# MB_power_supply.net
KiCad netlist of a schematic drawn in Altium Designer
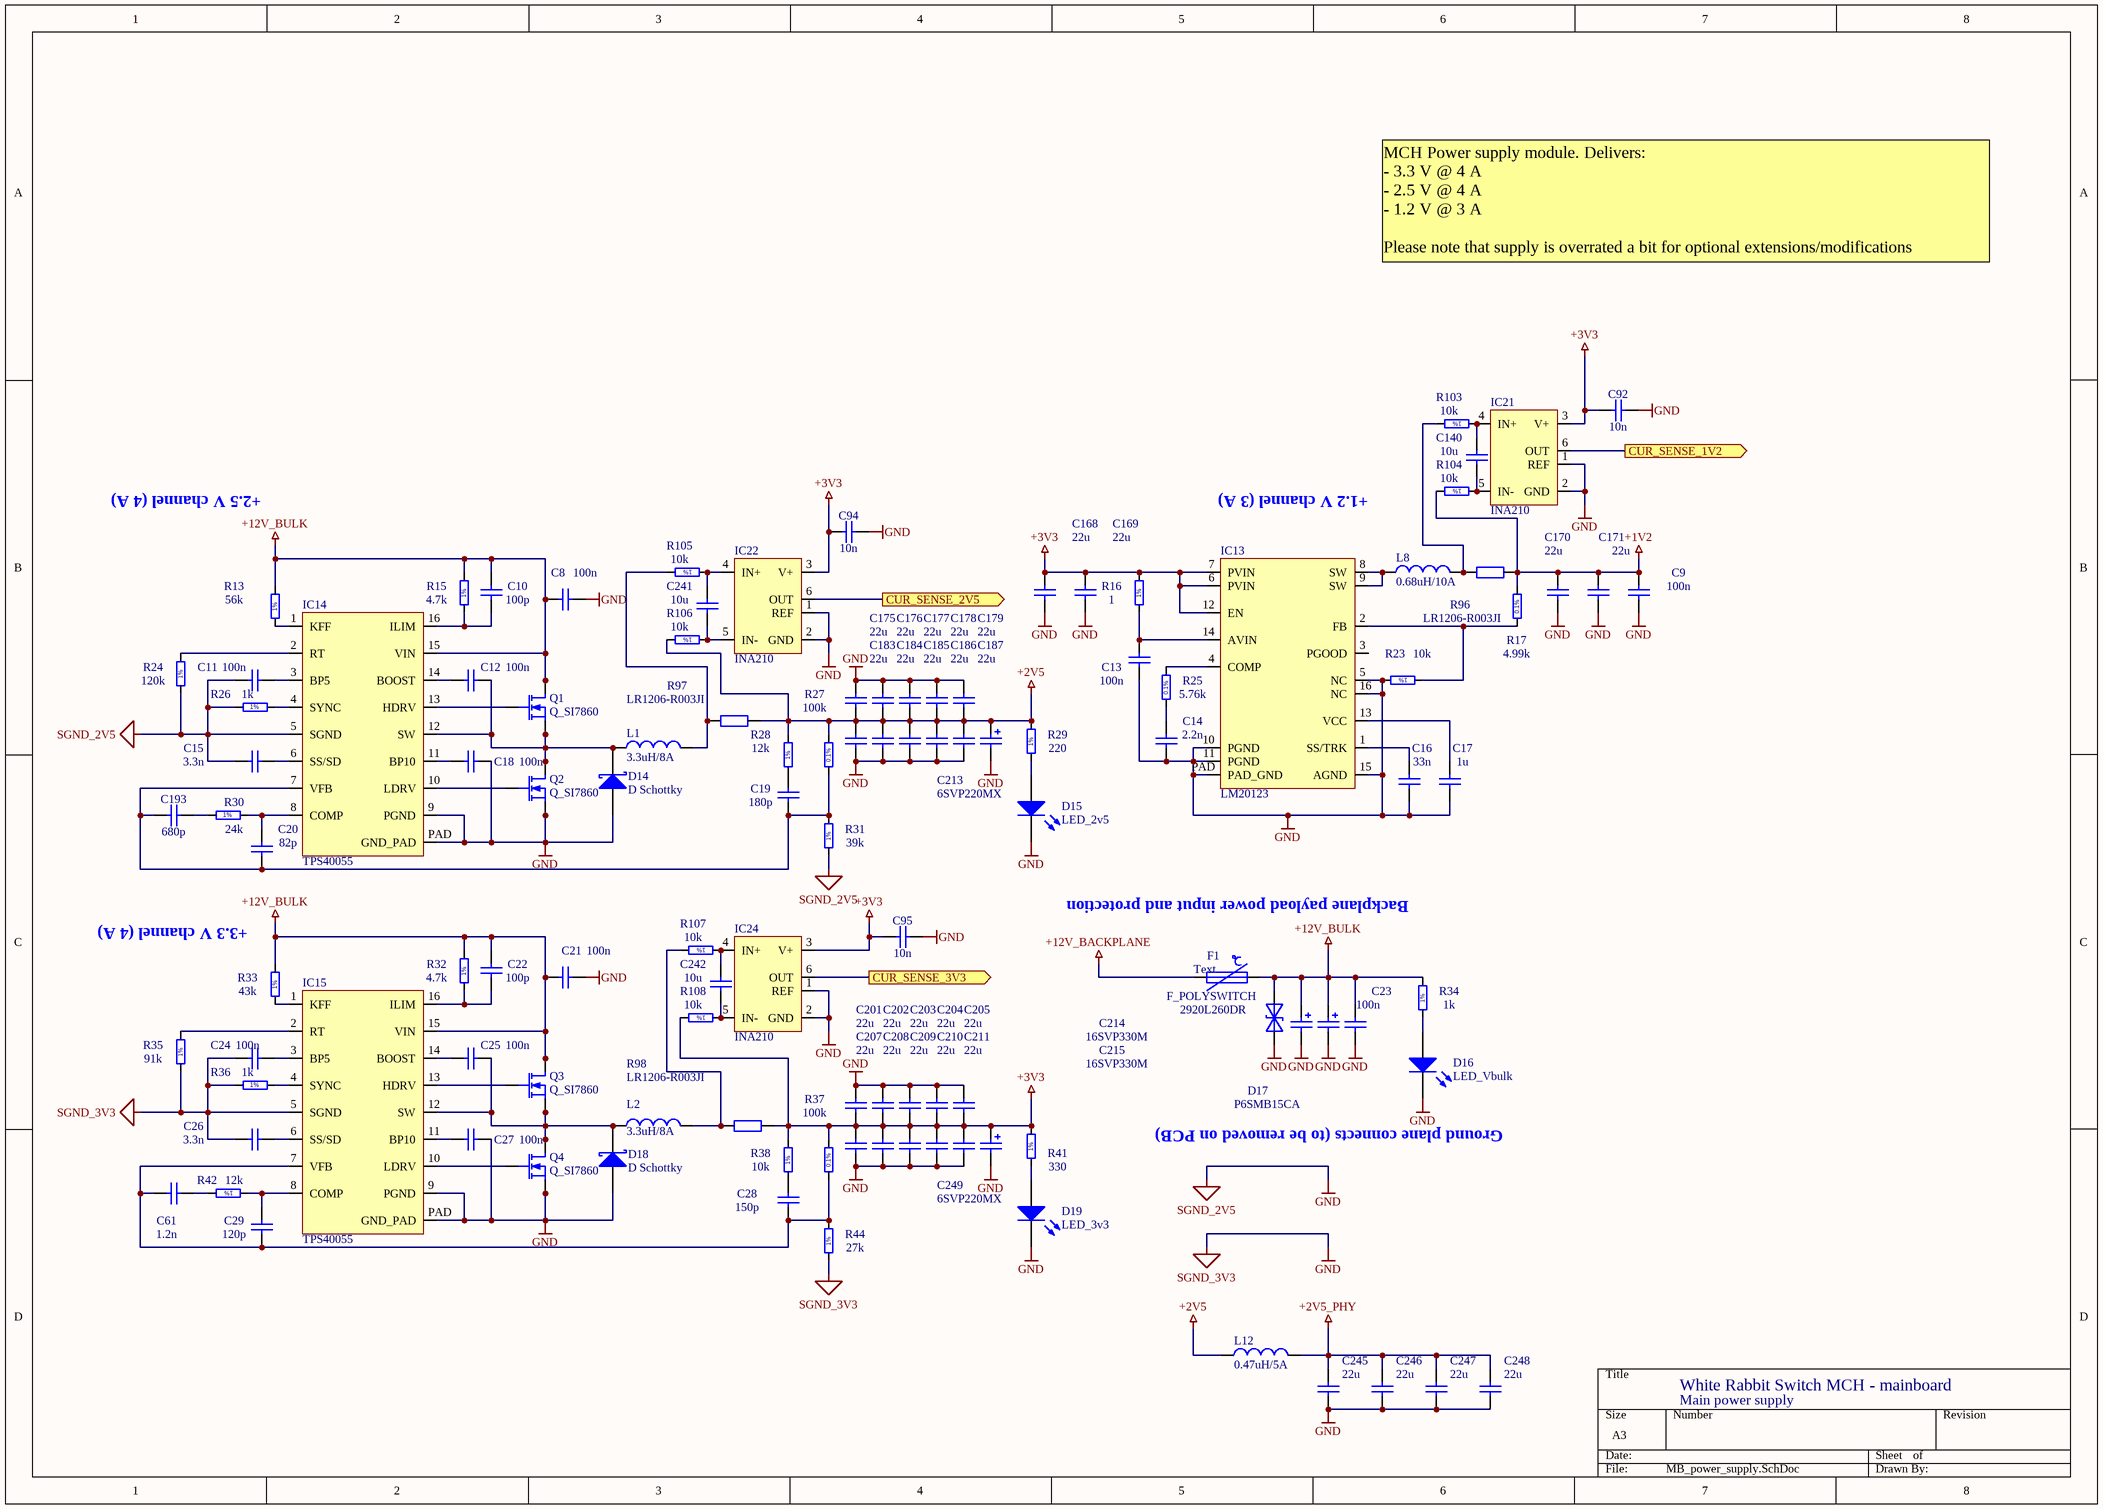
[diagram p0: MB_power_supply.SchDoc]

(export (version "E")
  (design (tool "Eeschema 10.0.6"))
  (components
    (comp (ref "C8")
      (value "100n")
      (footprint "CAPC1608X87N")
      (description "Non-polarised capacitor")
      (fields (field (name "PART NUMBER") "CC0603_100NF_50V_10%_X7R") (field (name "VOLTAGE") "50V"))
      (libsource (lib "Capacitors") (part "Capacitor - non polarized"))
    )
    (comp (ref "C9")
      (value "100n")
      (footprint "CAPC1608X87N")
      (description "Non-polarised capacitor")
      (fields (field (name "PART NUMBER") "CC0603_100NF_50V_10%_X7R") (field (name "VOLTAGE") "50V"))
      (libsource (lib "Capacitors") (part "Capacitor - non polarized"))
    )
    (comp (ref "C10")
      (value "100p")
      (footprint "CAPC1608X87N")
      (description "Non-polarised capacitor")
      (fields (field (name "PART NUMBER") "CC0603_100PF_50V_5%_NP0") (field (name "VOLTAGE") "50V"))
      (libsource (lib "Capacitors") (part "Capacitor - non polarized"))
    )
    (comp (ref "C11")
      (value "100n")
      (footprint "CAPC1608X87N")
      (description "Non-polarised capacitor")
      (fields (field (name "PART NUMBER") "CC0603_100NF_50V_10%_X7R") (field (name "VOLTAGE") "50V"))
      (libsource (lib "Capacitors") (part "Capacitor - non polarized"))
    )
    (comp (ref "C12")
      (value "100n")
      (footprint "CAPC1608X87N")
      (description "Non-polarised capacitor")
      (fields (field (name "PART NUMBER") "CC0603_100NF_50V_10%_X7R") (field (name "VOLTAGE") "50V"))
      (libsource (lib "Capacitors") (part "Capacitor - non polarized"))
    )
    (comp (ref "C13")
      (value "100n")
      (footprint "CAPC1608X87N")
      (description "Non-polarised capacitor")
      (fields (field (name "PART NUMBER") "CC0603_100NF_50V_10%_X7R") (field (name "VOLTAGE") "50V"))
      (libsource (lib "Capacitors") (part "Capacitor - non polarized"))
    )
    (comp (ref "C14")
      (value "2.2n")
      (footprint "CAPC1608X87N")
      (description "Non-polarised capacitor")
      (fields (field (name "PART NUMBER") "CC0603_2.2NF_50V_10%_X7R") (field (name "VOLTAGE") "50V"))
      (libsource (lib "Capacitors") (part "Capacitor - non polarized"))
    )
    (comp (ref "C15")
      (value "3.3n")
      (footprint "CAPC1608X87N")
      (description "Non-polarised capacitor")
      (fields (field (name "PART NUMBER") "CC0603_3.3NF_50V_10%_X7R") (field (name "VOLTAGE") "50V"))
      (libsource (lib "Capacitors") (part "Capacitor - non polarized"))
    )
    (comp (ref "C16")
      (value "33n")
      (footprint "CAPC1608X87N")
      (description "Non-polarised capacitor")
      (fields (field (name "PART NUMBER") "CC0603_33NF_25V_10%_X7R") (field (name "VOLTAGE") "25V"))
      (libsource (lib "Capacitors") (part "Capacitor - non polarized"))
    )
    (comp (ref "C17")
      (value "1u")
      (footprint "CAPC1608X87N")
      (description "Non-polarised capacitor")
      (fields (field (name "PART NUMBER") "CC0603_1.0uF_16V_10%_X7R") (field (name "VOLTAGE") "16V"))
      (libsource (lib "Capacitors") (part "Capacitor - non polarized"))
    )
    (comp (ref "C18")
      (value "100n")
      (footprint "CAPC1608X87N")
      (description "Non-polarised capacitor")
      (fields (field (name "PART NUMBER") "CC0603_100NF_50V_10%_X7R") (field (name "VOLTAGE") "50V"))
      (libsource (lib "Capacitors") (part "Capacitor - non polarized"))
    )
    (comp (ref "C19")
      (value "180p")
      (footprint "CAPC1608X87N")
      (description "Non-polarised capacitor")
      (fields (field (name "PART NUMBER") "CC0603_180PF_50V_5%_NP0") (field (name "VOLTAGE") "50V"))
      (libsource (lib "Capacitors") (part "Capacitor - non polarized"))
    )
    (comp (ref "C20")
      (value "82p")
      (footprint "CAPC1608X87N")
      (description "Non-polarised capacitor")
      (fields (field (name "PART NUMBER") "CC0603_82PF_50V_5%_NP0") (field (name "VOLTAGE") "50V"))
      (libsource (lib "Capacitors") (part "Capacitor - non polarized"))
    )
    (comp (ref "C21")
      (value "100n")
      (footprint "CAPC1608X87N")
      (description "Non-polarised capacitor")
      (fields (field (name "PART NUMBER") "CC0603_100NF_50V_10%_X7R") (field (name "VOLTAGE") "50V"))
      (libsource (lib "Capacitors") (part "Capacitor - non polarized"))
    )
    (comp (ref "C22")
      (value "100p")
      (footprint "CAPC1608X87N")
      (description "Non-polarised capacitor")
      (fields (field (name "PART NUMBER") "CC0603_100PF_50V_5%_NP0") (field (name "VOLTAGE") "50V"))
      (libsource (lib "Capacitors") (part "Capacitor - non polarized"))
    )
    (comp (ref "C23")
      (value "100n")
      (footprint "CAPC1608X87N")
      (description "Non-polarised capacitor")
      (fields (field (name "PART NUMBER") "CC0603_100NF_50V_10%_X7R") (field (name "VOLTAGE") "50V"))
      (libsource (lib "Capacitors") (part "Capacitor - non polarized"))
    )
    (comp (ref "C24")
      (value "100n")
      (footprint "CAPC1608X87N")
      (description "Non-polarised capacitor")
      (fields (field (name "PART NUMBER") "CC0603_100NF_50V_10%_X7R") (field (name "VOLTAGE") "50V"))
      (libsource (lib "Capacitors") (part "Capacitor - non polarized"))
    )
    (comp (ref "C25")
      (value "100n")
      (footprint "CAPC1608X87N")
      (description "Non-polarised capacitor")
      (fields (field (name "PART NUMBER") "CC0603_100NF_50V_10%_X7R") (field (name "VOLTAGE") "50V"))
      (libsource (lib "Capacitors") (part "Capacitor - non polarized"))
    )
    (comp (ref "C26")
      (value "3.3n")
      (footprint "CAPC1608X87N")
      (description "Non-polarised capacitor")
      (fields (field (name "PART NUMBER") "CC0603_3.3NF_50V_10%_X7R") (field (name "VOLTAGE") "50V"))
      (libsource (lib "Capacitors") (part "Capacitor - non polarized"))
    )
    (comp (ref "C27")
      (value "100n")
      (footprint "CAPC1608X87N")
      (description "Non-polarised capacitor")
      (fields (field (name "PART NUMBER") "CC0603_100NF_50V_10%_X7R") (field (name "VOLTAGE") "50V"))
      (libsource (lib "Capacitors") (part "Capacitor - non polarized"))
    )
    (comp (ref "C28")
      (value "150p")
      (footprint "CAPC1608X87N")
      (description "Non-polarised capacitor")
      (fields (field (name "PART NUMBER") "CC0603_150PF_50V_5%_NP0") (field (name "VOLTAGE") "50V"))
      (libsource (lib "Capacitors") (part "Capacitor - non polarized"))
    )
    (comp (ref "C29")
      (value "120p")
      (footprint "CAPC1608X87N")
      (description "Non-polarised capacitor")
      (fields (field (name "PART NUMBER") "CC0603_120PF_50V_5%_NP0") (field (name "VOLTAGE") "50V"))
      (libsource (lib "Capacitors") (part "Capacitor - non polarized"))
    )
    (comp (ref "C61")
      (value "1.2n")
      (footprint "CAPC1608X87N")
      (description "Non-polarised capacitor")
      (fields (field (name "PART NUMBER") "CC0603_1.2NF_50V_10%_X7R") (field (name "VOLTAGE") "50V"))
      (libsource (lib "Capacitors") (part "Capacitor - non polarized"))
    )
    (comp (ref "C92")
      (value "10n")
      (footprint "CAPC1608X87N")
      (description "Non-polarised capacitor")
      (fields (field (name "PART NUMBER") "CC0603_10NF_50V_10%_X7R") (field (name "VOLTAGE") "50V"))
      (libsource (lib "Capacitors") (part "Capacitor - non polarized"))
    )
    (comp (ref "C94")
      (value "10n")
      (footprint "CAPC1608X87N")
      (description "Non-polarised capacitor")
      (fields (field (name "PART NUMBER") "CC0603_10NF_50V_10%_X7R") (field (name "VOLTAGE") "50V"))
      (libsource (lib "Capacitors") (part "Capacitor - non polarized"))
    )
    (comp (ref "C95")
      (value "10n")
      (footprint "CAPC1608X87N")
      (description "Non-polarised capacitor")
      (fields (field (name "PART NUMBER") "CC0603_10NF_50V_10%_X7R") (field (name "VOLTAGE") "50V"))
      (libsource (lib "Capacitors") (part "Capacitor - non polarized"))
    )
    (comp (ref "C140")
      (value "10u")
      (footprint "CAPC1608X87N")
      (description "Non-polarised capacitor")
      (fields (field (name "PART NUMBER") "CC0603_10uF_6.3V_20%_X5R") (field (name "VOLTAGE") "6.3V"))
      (libsource (lib "Capacitors") (part "Capacitor - non polarized"))
    )
    (comp (ref "C168")
      (value "22u")
      (footprint "CC3216-1206")
      (description "Capacitor")
      (fields (field (name "Comment") "Cap"))
      (libsource (lib "wr_switch") (part "Cap"))
    )
    (comp (ref "C169")
      (value "22u")
      (footprint "CC3216-1206")
      (description "Capacitor")
      (fields (field (name "Comment") "Cap"))
      (libsource (lib "wr_switch") (part "Cap"))
    )
    (comp (ref "C170")
      (value "22u")
      (footprint "CC3216-1206")
      (description "Capacitor")
      (fields (field (name "Comment") "Cap"))
      (libsource (lib "wr_switch") (part "Cap"))
    )
    (comp (ref "C171")
      (value "22u")
      (footprint "CC3216-1206")
      (description "Capacitor")
      (fields (field (name "Comment") "Cap"))
      (libsource (lib "wr_switch") (part "Cap"))
    )
    (comp (ref "C175")
      (value "22u")
      (footprint "CC3216-1206")
      (description "Capacitor")
      (fields (field (name "Comment") "Cap"))
      (libsource (lib "wr_switch") (part "Cap"))
    )
    (comp (ref "C176")
      (value "22u")
      (footprint "CC3216-1206")
      (description "Capacitor")
      (fields (field (name "Comment") "Cap"))
      (libsource (lib "wr_switch") (part "Cap"))
    )
    (comp (ref "C177")
      (value "22u")
      (footprint "CC3216-1206")
      (description "Capacitor")
      (fields (field (name "Comment") "Cap"))
      (libsource (lib "wr_switch") (part "Cap"))
    )
    (comp (ref "C178")
      (value "22u")
      (footprint "CC3216-1206")
      (description "Capacitor")
      (fields (field (name "Comment") "Cap"))
      (libsource (lib "wr_switch") (part "Cap"))
    )
    (comp (ref "C179")
      (value "22u")
      (footprint "CC3216-1206")
      (description "Capacitor")
      (fields (field (name "Comment") "Cap"))
      (libsource (lib "wr_switch") (part "Cap"))
    )
    (comp (ref "C183")
      (value "22u")
      (footprint "CC3216-1206")
      (description "Capacitor")
      (fields (field (name "Comment") "Cap"))
      (libsource (lib "wr_switch") (part "Cap"))
    )
    (comp (ref "C184")
      (value "22u")
      (footprint "CC3216-1206")
      (description "Capacitor")
      (fields (field (name "Comment") "Cap"))
      (libsource (lib "wr_switch") (part "Cap"))
    )
    (comp (ref "C185")
      (value "22u")
      (footprint "CC3216-1206")
      (description "Capacitor")
      (fields (field (name "Comment") "Cap"))
      (libsource (lib "wr_switch") (part "Cap"))
    )
    (comp (ref "C186")
      (value "22u")
      (footprint "CC3216-1206")
      (description "Capacitor")
      (fields (field (name "Comment") "Cap"))
      (libsource (lib "wr_switch") (part "Cap"))
    )
    (comp (ref "C187")
      (value "22u")
      (footprint "CC3216-1206")
      (description "Capacitor")
      (fields (field (name "Comment") "Cap"))
      (libsource (lib "wr_switch") (part "Cap"))
    )
    (comp (ref "C193")
      (value "680p")
      (footprint "CAPC1608X87N")
      (description "Non-polarised capacitor")
      (fields (field (name "PART NUMBER") "CC0603_680PF_50V_5%_NP0") (field (name "VOLTAGE") "50V"))
      (libsource (lib "Capacitors") (part "Capacitor - non polarized"))
    )
    (comp (ref "C201")
      (value "22u")
      (footprint "CC3216-1206")
      (description "Capacitor")
      (fields (field (name "Comment") "Cap"))
      (libsource (lib "wr_switch") (part "Cap"))
    )
    (comp (ref "C202")
      (value "22u")
      (footprint "CC3216-1206")
      (description "Capacitor")
      (fields (field (name "Comment") "Cap"))
      (libsource (lib "wr_switch") (part "Cap"))
    )
    (comp (ref "C203")
      (value "22u")
      (footprint "CC3216-1206")
      (description "Capacitor")
      (fields (field (name "Comment") "Cap"))
      (libsource (lib "wr_switch") (part "Cap"))
    )
    (comp (ref "C204")
      (value "22u")
      (footprint "CC3216-1206")
      (description "Capacitor")
      (fields (field (name "Comment") "Cap"))
      (libsource (lib "wr_switch") (part "Cap"))
    )
    (comp (ref "C205")
      (value "22u")
      (footprint "CC3216-1206")
      (description "Capacitor")
      (fields (field (name "Comment") "Cap"))
      (libsource (lib "wr_switch") (part "Cap"))
    )
    (comp (ref "C207")
      (value "22u")
      (footprint "CC3216-1206")
      (description "Capacitor")
      (fields (field (name "Comment") "Cap"))
      (libsource (lib "wr_switch") (part "Cap"))
    )
    (comp (ref "C208")
      (value "22u")
      (footprint "CC3216-1206")
      (description "Capacitor")
      (fields (field (name "Comment") "Cap"))
      (libsource (lib "wr_switch") (part "Cap"))
    )
    (comp (ref "C209")
      (value "22u")
      (footprint "CC3216-1206")
      (description "Capacitor")
      (fields (field (name "Comment") "Cap"))
      (libsource (lib "wr_switch") (part "Cap"))
    )
    (comp (ref "C210")
      (value "22u")
      (footprint "CC3216-1206")
      (description "Capacitor")
      (fields (field (name "Comment") "Cap"))
      (libsource (lib "wr_switch") (part "Cap"))
    )
    (comp (ref "C211")
      (value "22u")
      (footprint "CC3216-1206")
      (description "Capacitor")
      (fields (field (name "Comment") "Cap"))
      (libsource (lib "wr_switch") (part "Cap"))
    )
    (comp (ref "C213")
      (value "6SVP220MX")
      (footprint "OSCON_E7")
      (description "Polarized Capacitor (Radial)")
      (fields (field (name "Comment") "Cap Pol1"))
      (libsource (lib "wr_switch") (part "Cap Pol1"))
    )
    (comp (ref "C214")
      (value "16SVP330M")
      (footprint "OSCON_F12")
      (description "Polarized Capacitor (Radial)")
      (fields (field (name "Comment") "Cap Pol1"))
      (libsource (lib "wr_switch") (part "Cap Pol1"))
    )
    (comp (ref "C215")
      (value "16SVP330M")
      (footprint "OSCON_F12")
      (description "Polarized Capacitor (Radial)")
      (fields (field (name "Comment") "Cap Pol1"))
      (libsource (lib "wr_switch") (part "Cap Pol1"))
    )
    (comp (ref "C241")
      (value "10u")
      (footprint "CAPC1608X87N")
      (description "Non-polarised capacitor")
      (fields (field (name "PART NUMBER") "CC0603_10uF_6.3V_20%_X5R") (field (name "VOLTAGE") "6.3V"))
      (libsource (lib "Capacitors") (part "Capacitor - non polarized"))
    )
    (comp (ref "C242")
      (value "10u")
      (footprint "CAPC1608X87N")
      (description "Non-polarised capacitor")
      (fields (field (name "PART NUMBER") "CC0603_10uF_6.3V_20%_X5R") (field (name "VOLTAGE") "6.3V"))
      (libsource (lib "Capacitors") (part "Capacitor - non polarized"))
    )
    (comp (ref "C245")
      (value "22u")
      (footprint "CC3216-1206")
      (description "Capacitor")
      (fields (field (name "Comment") "Cap"))
      (libsource (lib "wr_switch") (part "Cap"))
    )
    (comp (ref "C246")
      (value "22u")
      (footprint "CC3216-1206")
      (description "Capacitor")
      (fields (field (name "Comment") "Cap"))
      (libsource (lib "wr_switch") (part "Cap"))
    )
    (comp (ref "C247")
      (value "22u")
      (footprint "CC3216-1206")
      (description "Capacitor")
      (fields (field (name "Comment") "Cap"))
      (libsource (lib "wr_switch") (part "Cap"))
    )
    (comp (ref "C248")
      (value "22u")
      (footprint "CC3216-1206")
      (description "Capacitor")
      (fields (field (name "Comment") "Cap"))
      (libsource (lib "wr_switch") (part "Cap"))
    )
    (comp (ref "C249")
      (value "6SVP220MX")
      (footprint "OSCON_E7")
      (description "Polarized Capacitor (Radial)")
      (fields (field (name "Comment") "Cap Pol1"))
      (libsource (lib "wr_switch") (part "Cap Pol1"))
    )
    (comp (ref "D14")
      (value "D Schottky")
      (footprint "CD3216-1206")
      (description "Schottky Diode")
      (libsource (lib "wr_switch") (part "D Schottky"))
    )
    (comp (ref "D15")
      (value "LED_2v5")
      (footprint "CD1608-0603")
      (description "Red chip LED")
      (libsource (lib "wr_switch") (part "LED0"))
    )
    (comp (ref "D16")
      (value "LED_Vbulk")
      (footprint "CD1608-0603")
      (description "Red chip LED")
      (libsource (lib "wr_switch") (part "LED0"))
    )
    (comp (ref "D17")
      (value "P6SMB15CA")
      (footprint "footprints:DO-214AA/SMB")
      (description "transil 600W")
      (libsource (lib "wr_switch") (part "D_TRANSIL_SMD_0.6KW"))
    )
    (comp (ref "D18")
      (value "D Schottky")
      (footprint "CD3216-1206")
      (description "Schottky Diode")
      (libsource (lib "wr_switch") (part "D Schottky"))
    )
    (comp (ref "D19")
      (value "LED_3v3")
      (footprint "CD1608-0603")
      (description "Red chip LED")
      (libsource (lib "wr_switch") (part "LED0"))
    )
    (comp (ref "F1")
      (value "F_POLYSWITCH")
      (footprint "PTC_SMD_1812")
      (description "polymer FUSE")
      (fields (field (name "ALTIUM_VALUE") "2920L260DR"))
      (libsource (lib "wr_switch") (part "F_POLYSWITCH"))
    )
    (comp (ref "IC13")
      (value "LM20123")
      (footprint "eTSSOP_16_MX")
      (description "National Semiconductor 3A integrated synchronous buck converter")
      (libsource (lib "wr_switch") (part "LM20123"))
    )
    (comp (ref "IC14")
      (value "TPS40055")
      (footprint "TI_PWP_16")
      (description "TI synchronous buck controller")
      (fields (field (name "Comment") "TPS4005X"))
      (libsource (lib "wr_switch") (part "TPS4005X"))
    )
    (comp (ref "IC15")
      (value "TPS40055")
      (footprint "TI_PWP_16")
      (description "TI synchronous buck controller")
      (fields (field (name "Comment") "TPS4005X"))
      (libsource (lib "wr_switch") (part "TPS4005X"))
    )
    (comp (ref "IC21")
      (value "INA210")
      (footprint "TI_6sc70")
      (description "High/low side current monitor")
      (libsource (lib "wr_switch") (part "INA210_214"))
    )
    (comp (ref "IC22")
      (value "INA210")
      (footprint "TI_6sc70")
      (description "High/low side current monitor")
      (libsource (lib "wr_switch") (part "INA210_214"))
    )
    (comp (ref "IC24")
      (value "INA210")
      (footprint "TI_6sc70")
      (description "High/low side current monitor")
      (libsource (lib "wr_switch") (part "INA210_214"))
    )
    (comp (ref "L1")
      (value "3.3uH/8A")
      (footprint "IHLP2525")
      (description "Vishay 16A 2.2u inductor")
      (libsource (lib "wr_switch") (part "L_IHLP2525_0.68u"))
    )
    (comp (ref "L2")
      (value "3.3uH/8A")
      (footprint "IHLP2525")
      (description "Vishay 16A 2.2u inductor")
      (libsource (lib "wr_switch") (part "L_IHLP2525_0.68u"))
    )
    (comp (ref "L8")
      (value "0.68uH/10A")
      (footprint "IHLP2525")
      (description "Vishay 16A 2.2u inductor")
      (libsource (lib "wr_switch") (part "L_IHLP2525_0.68u"))
    )
    (comp (ref "L12")
      (value "0.47uH/5A")
      (footprint "IND_WURTH_744042_MH")
      (description "Wuerth small footprint SMD power inductor")
      (libsource (lib "wr_switch") (part "L_WUERTH_744043"))
    )
    (comp (ref "Q1")
      (value "Q_SI7860")
      (footprint "SOIC127P600-8AL")
      (description "18A 8mOhm N-Channel MOSFET")
      (libsource (lib "wr_switch") (part "Q_SI7860"))
    )
    (comp (ref "Q2")
      (value "Q_SI7860")
      (footprint "SOIC127P600-8AL")
      (description "18A 8mOhm N-Channel MOSFET")
      (libsource (lib "wr_switch") (part "Q_SI7860"))
    )
    (comp (ref "Q3")
      (value "Q_SI7860")
      (footprint "SOIC127P600-8AL")
      (description "18A 8mOhm N-Channel MOSFET")
      (libsource (lib "wr_switch") (part "Q_SI7860"))
    )
    (comp (ref "Q4")
      (value "Q_SI7860")
      (footprint "SOIC127P600-8AL")
      (description "18A 8mOhm N-Channel MOSFET")
      (libsource (lib "wr_switch") (part "Q_SI7860"))
    )
    (comp (ref "R13")
      (value "56k")
      (footprint "RESC1608X55N")
      (description "Resistor - 1%")
      (fields (field (name "PART NUMBER") "R0603_56K_1%_0.1W_100PPM") (field (name "POWER") "0.1W"))
      (libsource (lib "Resistors") (part "Resistor - 1%"))
    )
    (comp (ref "R15")
      (value "4.7k")
      (footprint "RESC1608X55N")
      (description "Resistor - 1%")
      (fields (field (name "PART NUMBER") "R0603_4K7_1%_0.1W_100PPM") (field (name "POWER") "0.1W"))
      (libsource (lib "Resistors") (part "Resistor - 1%"))
    )
    (comp (ref "R16")
      (value "1")
      (footprint "RESC1608X55N")
      (description "Resistor - 1%")
      (fields (field (name "PART NUMBER") "R0603_1R_1%_0.1W_100PPM") (field (name "POWER") "0.1W"))
      (libsource (lib "Resistors") (part "Resistor - 1%"))
    )
    (comp (ref "R17")
      (value "4.99k")
      (footprint "RESC1608X55N")
      (description "Resistor - 0.1%")
      (fields (field (name "PART NUMBER") "R0603_4K99_0.1%_0.063W_10PPM") (field (name "POWER") "0.063W"))
      (libsource (lib "Resistors") (part "Resistor - 0.1%"))
    )
    (comp (ref "R23")
      (value "10k")
      (footprint "RESC1608X55N")
      (description "Resistor - 1%")
      (fields (field (name "PART NUMBER") "R0603_10K_1%_0.1W_100PPM") (field (name "POWER") "0.1W"))
      (libsource (lib "Resistors") (part "Resistor - 1%"))
    )
    (comp (ref "R24")
      (value "120k")
      (footprint "RESC1608X55N")
      (description "Resistor - 1%")
      (fields (field (name "PART NUMBER") "R0603_120K_1%_0.1W_100PPM") (field (name "POWER") "0.1W"))
      (libsource (lib "Resistors") (part "Resistor - 1%"))
    )
    (comp (ref "R25")
      (value "5.76k")
      (footprint "RESC1608X55N")
      (description "Resistor - 0.1%")
      (fields (field (name "PART NUMBER") "R0603_5K76_0.1%_0.063W_10PPM") (field (name "POWER") "0.063W"))
      (libsource (lib "Resistors") (part "Resistor - 0.1%"))
    )
    (comp (ref "R26")
      (value "1k")
      (footprint "RESC1608X55N")
      (description "Resistor - 1%")
      (fields (field (name "PART NUMBER") "R0603_1K_1%_0.1W_100PPM") (field (name "POWER") "0.1W"))
      (libsource (lib "Resistors") (part "Resistor - 1%"))
    )
    (comp (ref "R27")
      (value "100k")
      (footprint "RESC1608X55N")
      (description "Resistor - 0.1%")
      (fields (field (name "PART NUMBER") "R0603_100K_0.1%_0.063W_10PPM") (field (name "POWER") "0.063W"))
      (libsource (lib "Resistors") (part "Resistor - 0.1%"))
    )
    (comp (ref "R28")
      (value "12k")
      (footprint "RESC1608X55N")
      (description "Resistor - 1%")
      (fields (field (name "PART NUMBER") "R0603_12K_1%_0.1W_100PPM") (field (name "POWER") "0.1W"))
      (libsource (lib "Resistors") (part "Resistor - 1%"))
    )
    (comp (ref "R29")
      (value "220")
      (footprint "RESC1608X55N")
      (description "Resistor - 1%")
      (fields (field (name "PART NUMBER") "R0603_220R_1%_0.1W_100PPM") (field (name "POWER") "0.1W"))
      (libsource (lib "Resistors") (part "Resistor - 1%"))
    )
    (comp (ref "R30")
      (value "24k")
      (footprint "RESC1608X55N")
      (description "Resistor - 1%")
      (fields (field (name "PART NUMBER") "R0603_24K_1%_0.1W_100PPM") (field (name "POWER") "0.1W"))
      (libsource (lib "Resistors") (part "Resistor - 1%"))
    )
    (comp (ref "R31")
      (value "39k")
      (footprint "RESC1608X55N")
      (description "Resistor - 1%")
      (fields (field (name "PART NUMBER") "R0603_39K_1%_0.1W_100PPM") (field (name "POWER") "0.1W"))
      (libsource (lib "Resistors") (part "Resistor - 1%"))
    )
    (comp (ref "R32")
      (value "4.7k")
      (footprint "RESC1608X55N")
      (description "Resistor - 1%")
      (fields (field (name "PART NUMBER") "R0603_4K7_1%_0.1W_100PPM") (field (name "POWER") "0.1W"))
      (libsource (lib "Resistors") (part "Resistor - 1%"))
    )
    (comp (ref "R33")
      (value "43k")
      (footprint "RESC1608X55N")
      (description "Resistor - 1%")
      (fields (field (name "PART NUMBER") "R0603_43K_1%_0.1W_100PPM") (field (name "POWER") "0.1W"))
      (libsource (lib "Resistors") (part "Resistor - 1%"))
    )
    (comp (ref "R34")
      (value "1k")
      (footprint "RESC1005X40N")
      (description "Resistor - 1%")
      (fields (field (name "PART NUMBER") "R0402_1K_1%_0.0625W_100PPM") (field (name "POWER") "0.0625W"))
      (libsource (lib "Resistors") (part "Resistor - 1%"))
    )
    (comp (ref "R35")
      (value "91k")
      (footprint "RESC1608X55N")
      (description "Resistor - 1%")
      (fields (field (name "PART NUMBER") "R0603_91K_1%_0.1W_100PPM") (field (name "POWER") "0.1W"))
      (libsource (lib "Resistors") (part "Resistor - 1%"))
    )
    (comp (ref "R36")
      (value "1k")
      (footprint "RESC1608X55N")
      (description "Resistor - 1%")
      (fields (field (name "PART NUMBER") "R0603_1K_1%_0.1W_100PPM") (field (name "POWER") "0.1W"))
      (libsource (lib "Resistors") (part "Resistor - 1%"))
    )
    (comp (ref "R37")
      (value "100k")
      (footprint "RESC1608X55N")
      (description "Resistor - 0.1%")
      (fields (field (name "PART NUMBER") "R0603_100K_0.1%_0.063W_10PPM") (field (name "POWER") "0.063W"))
      (libsource (lib "Resistors") (part "Resistor - 0.1%"))
    )
    (comp (ref "R38")
      (value "10k")
      (footprint "RESC1608X55N")
      (description "Resistor - 1%")
      (fields (field (name "PART NUMBER") "R0603_10K_1%_0.1W_100PPM") (field (name "POWER") "0.1W"))
      (libsource (lib "Resistors") (part "Resistor - 1%"))
    )
    (comp (ref "R41")
      (value "330")
      (footprint "RESC1608X55N")
      (description "Resistor - 1%")
      (fields (field (name "PART NUMBER") "R0603_330R_1%_0.1W_100PPM") (field (name "POWER") "0.1W"))
      (libsource (lib "Resistors") (part "Resistor - 1%"))
    )
    (comp (ref "R42")
      (value "12k")
      (footprint "RESC1608X55N")
      (description "Resistor - 1%")
      (fields (field (name "PART NUMBER") "R0603_12K_1%_0.1W_100PPM") (field (name "POWER") "0.1W"))
      (libsource (lib "Resistors") (part "Resistor - 1%"))
    )
    (comp (ref "R44")
      (value "27k")
      (footprint "RESC1608X55N")
      (description "Resistor - 1%")
      (fields (field (name "PART NUMBER") "R0603_27K_1%_0.1W_100PPM") (field (name "POWER") "0.1W"))
      (libsource (lib "Resistors") (part "Resistor - 1%"))
    )
    (comp (ref "R96")
      (value "LR1206-R003JI")
      (footprint "CR3216-1206")
      (description "Resistor")
      (fields (field (name "Comment") "0.003R"))
      (libsource (lib "Miscellaneous Devices") (part "Res2"))
    )
    (comp (ref "R97")
      (value "LR1206-R003JI")
      (footprint "CR3216-1206")
      (description "Resistor")
      (fields (field (name "Comment") "0.003R"))
      (libsource (lib "Miscellaneous Devices") (part "Res2"))
    )
    (comp (ref "R98")
      (value "LR1206-R003JI")
      (footprint "CR3216-1206")
      (description "Resistor")
      (fields (field (name "Comment") "0.003R"))
      (libsource (lib "Miscellaneous Devices") (part "Res2"))
    )
    (comp (ref "R103")
      (value "10k")
      (footprint "RESC1005X40N")
      (description "Resistor - 1%")
      (fields (field (name "PART NUMBER") "R0402_10K_1%_0.0625W_100PPM") (field (name "POWER") "0.0625W"))
      (libsource (lib "Resistors") (part "Resistor - 1%"))
    )
    (comp (ref "R104")
      (value "10k")
      (footprint "RESC1005X40N")
      (description "Resistor - 1%")
      (fields (field (name "PART NUMBER") "R0402_10K_1%_0.0625W_100PPM") (field (name "POWER") "0.0625W"))
      (libsource (lib "Resistors") (part "Resistor - 1%"))
    )
    (comp (ref "R105")
      (value "10k")
      (footprint "RESC1005X40N")
      (description "Resistor - 1%")
      (fields (field (name "PART NUMBER") "R0402_10K_1%_0.0625W_100PPM") (field (name "POWER") "0.0625W"))
      (libsource (lib "Resistors") (part "Resistor - 1%"))
    )
    (comp (ref "R106")
      (value "10k")
      (footprint "RESC1005X40N")
      (description "Resistor - 1%")
      (fields (field (name "PART NUMBER") "R0402_10K_1%_0.0625W_100PPM") (field (name "POWER") "0.0625W"))
      (libsource (lib "Resistors") (part "Resistor - 1%"))
    )
    (comp (ref "R107")
      (value "10k")
      (footprint "RESC1005X40N")
      (description "Resistor - 1%")
      (fields (field (name "PART NUMBER") "R0402_10K_1%_0.0625W_100PPM") (field (name "POWER") "0.0625W"))
      (libsource (lib "Resistors") (part "Resistor - 1%"))
    )
    (comp (ref "R108")
      (value "10k")
      (footprint "RESC1005X40N")
      (description "Resistor - 1%")
      (fields (field (name "PART NUMBER") "R0402_10K_1%_0.0625W_100PPM") (field (name "POWER") "0.0625W"))
      (libsource (lib "Resistors") (part "Resistor - 1%"))
    )
  )
  (nets
    (net (code "1") (name "+1V2") (class "Default")
      (node (ref "C170") (pin "2") (pinfunction "2_2") (pintype "passive"))
      (node (ref "C171") (pin "2") (pinfunction "2_2") (pintype "passive"))
      (node (ref "C9") (pin "2") (pinfunction "2_2") (pintype "passive"))
      (node (ref "R104") (pin "2") (pinfunction "2_2") (pintype "passive"))
      (node (ref "R17") (pin "2") (pinfunction "2_2") (pintype "passive"))
      (node (ref "R96") (pin "1") (pinfunction "1_1") (pintype "passive"))
    )
    (net (code "2") (name "+2V5") (class "Default")
      (node (ref "C175") (pin "1") (pinfunction "1_1") (pintype "passive"))
      (node (ref "C176") (pin "1") (pinfunction "1_1") (pintype "passive"))
      (node (ref "C177") (pin "1") (pinfunction "1_1") (pintype "passive"))
      (node (ref "C178") (pin "1") (pinfunction "1_1") (pintype "passive"))
      (node (ref "C179") (pin "1") (pinfunction "1_1") (pintype "passive"))
      (node (ref "C183") (pin "2") (pinfunction "2_2") (pintype "passive"))
      (node (ref "C184") (pin "2") (pinfunction "2_2") (pintype "passive"))
      (node (ref "C185") (pin "2") (pinfunction "2_2") (pintype "passive"))
      (node (ref "C186") (pin "2") (pinfunction "2_2") (pintype "passive"))
      (node (ref "C187") (pin "2") (pinfunction "2_2") (pintype "passive"))
      (node (ref "C213") (pin "1") (pinfunction "1_1") (pintype "passive"))
      (node (ref "L12") (pin "1") (pinfunction "1_1") (pintype "passive"))
      (node (ref "R106") (pin "2") (pinfunction "2_2") (pintype "passive"))
      (node (ref "R27") (pin "2") (pinfunction "2_2") (pintype "passive"))
      (node (ref "R28") (pin "2") (pinfunction "2_2") (pintype "passive"))
      (node (ref "R29") (pin "2") (pinfunction "2_2") (pintype "passive"))
      (node (ref "R97") (pin "1") (pinfunction "1_1") (pintype "passive"))
    )
    (net (code "3") (name "+2V5_PHY") (class "Default")
      (node (ref "C245") (pin "2") (pinfunction "2_2") (pintype "passive"))
      (node (ref "C246") (pin "2") (pinfunction "2_2") (pintype "passive"))
      (node (ref "C247") (pin "2") (pinfunction "2_2") (pintype "passive"))
      (node (ref "C248") (pin "2") (pinfunction "2_2") (pintype "passive"))
      (node (ref "L12") (pin "2") (pinfunction "2_2") (pintype "passive"))
    )
    (net (code "4") (name "+3V3") (class "Default")
      (node (ref "C168") (pin "2") (pinfunction "2_2") (pintype "passive"))
      (node (ref "C169") (pin "2") (pinfunction "2_2") (pintype "passive"))
      (node (ref "C201") (pin "2") (pinfunction "2_2") (pintype "passive"))
      (node (ref "C202") (pin "2") (pinfunction "2_2") (pintype "passive"))
      (node (ref "C203") (pin "2") (pinfunction "2_2") (pintype "passive"))
      (node (ref "C204") (pin "2") (pinfunction "2_2") (pintype "passive"))
      (node (ref "C205") (pin "2") (pinfunction "2_2") (pintype "passive"))
      (node (ref "C207") (pin "1") (pinfunction "1_1") (pintype "passive"))
      (node (ref "C208") (pin "1") (pinfunction "1_1") (pintype "passive"))
      (node (ref "C209") (pin "1") (pinfunction "1_1") (pintype "passive"))
      (node (ref "C210") (pin "1") (pinfunction "1_1") (pintype "passive"))
      (node (ref "C211") (pin "1") (pinfunction "1_1") (pintype "passive"))
      (node (ref "C249") (pin "1") (pinfunction "1_1") (pintype "passive"))
      (node (ref "C92") (pin "1") (pinfunction "1_1") (pintype "passive"))
      (node (ref "C94") (pin "1") (pinfunction "1_1") (pintype "passive"))
      (node (ref "C95") (pin "1") (pinfunction "1_1") (pintype "passive"))
      (node (ref "IC13") (pin "12") (pinfunction "EN_12") (pintype "passive"))
      (node (ref "IC13") (pin "6") (pinfunction "PVIN_6") (pintype "passive"))
      (node (ref "IC13") (pin "7") (pinfunction "PVIN_7") (pintype "passive"))
      (node (ref "IC21") (pin "3") (pinfunction "V+_3") (pintype "power_in"))
      (node (ref "IC22") (pin "3") (pinfunction "V+_3") (pintype "power_in"))
      (node (ref "IC24") (pin "3") (pinfunction "V+_3") (pintype "power_in"))
      (node (ref "R108") (pin "2") (pinfunction "2_2") (pintype "passive"))
      (node (ref "R16") (pin "2") (pinfunction "2_2") (pintype "passive"))
      (node (ref "R37") (pin "2") (pinfunction "2_2") (pintype "passive"))
      (node (ref "R38") (pin "2") (pinfunction "2_2") (pintype "passive"))
      (node (ref "R41") (pin "2") (pinfunction "2_2") (pintype "passive"))
      (node (ref "R98") (pin "1") (pinfunction "1_1") (pintype "passive"))
    )
    (net (code "5") (name "+12V_BACKPLANE") (class "Default")
      (node (ref "F1") (pin "1") (pinfunction "1_1") (pintype "passive"))
    )
    (net (code "6") (name "+12V_BULK") (class "Default")
      (node (ref "C10") (pin "2") (pinfunction "2_2") (pintype "passive"))
      (node (ref "C21") (pin "1") (pinfunction "1_1") (pintype "passive"))
      (node (ref "C214") (pin "1") (pinfunction "1_1") (pintype "passive"))
      (node (ref "C215") (pin "1") (pinfunction "1_1") (pintype "passive"))
      (node (ref "C22") (pin "2") (pinfunction "2_2") (pintype "passive"))
      (node (ref "C23") (pin "2") (pinfunction "2_2") (pintype "passive"))
      (node (ref "C8") (pin "1") (pinfunction "1_1") (pintype "passive"))
      (node (ref "D17") (pin "K") (pinfunction "K_K") (pintype "passive"))
      (node (ref "F1") (pin "2") (pinfunction "2_2") (pintype "passive"))
      (node (ref "IC14") (pin "15") (pinfunction "VIN_15") (pintype "passive"))
      (node (ref "IC15") (pin "15") (pinfunction "VIN_15") (pintype "passive"))
      (node (ref "Q1") (pin "5") (pinfunction "D_5") (pintype "passive"))
      (node (ref "Q1") (pin "6") (pinfunction "D_6") (pintype "passive"))
      (node (ref "Q1") (pin "7") (pinfunction "D_7") (pintype "passive"))
      (node (ref "Q1") (pin "8") (pinfunction "D_8") (pintype "passive"))
      (node (ref "Q3") (pin "5") (pinfunction "D_5") (pintype "passive"))
      (node (ref "Q3") (pin "6") (pinfunction "D_6") (pintype "passive"))
      (node (ref "Q3") (pin "7") (pinfunction "D_7") (pintype "passive"))
      (node (ref "Q3") (pin "8") (pinfunction "D_8") (pintype "passive"))
      (node (ref "R13") (pin "2") (pinfunction "2_2") (pintype "passive"))
      (node (ref "R15") (pin "2") (pinfunction "2_2") (pintype "passive"))
      (node (ref "R32") (pin "2") (pinfunction "2_2") (pintype "passive"))
      (node (ref "R33") (pin "2") (pinfunction "2_2") (pintype "passive"))
      (node (ref "R34") (pin "2") (pinfunction "2_2") (pintype "passive"))
    )
    (net (code "7") (name "/CUR_SENSE_1V2") (class "Default")
      (node (ref "IC21") (pin "6") (pinfunction "OUT_6") (pintype "power_in"))
    )
    (net (code "8") (name "/CUR_SENSE_2V5") (class "Default")
      (node (ref "IC22") (pin "6") (pinfunction "OUT_6") (pintype "power_in"))
    )
    (net (code "9") (name "/CUR_SENSE_3V3") (class "Default")
      (node (ref "IC24") (pin "6") (pinfunction "OUT_6") (pintype "power_in"))
    )
    (net (code "10") (name "GND") (class "Default")
      (node (ref "C11") (pin "1") (pinfunction "1_1") (pintype "passive"))
      (node (ref "C13") (pin "1") (pinfunction "1_1") (pintype "passive"))
      (node (ref "C14") (pin "1") (pinfunction "1_1") (pintype "passive"))
      (node (ref "C15") (pin "1") (pinfunction "1_1") (pintype "passive"))
      (node (ref "C16") (pin "1") (pinfunction "1_1") (pintype "passive"))
      (node (ref "C168") (pin "1") (pinfunction "1_1") (pintype "passive"))
      (node (ref "C169") (pin "1") (pinfunction "1_1") (pintype "passive"))
      (node (ref "C17") (pin "1") (pinfunction "1_1") (pintype "passive"))
      (node (ref "C170") (pin "1") (pinfunction "1_1") (pintype "passive"))
      (node (ref "C171") (pin "1") (pinfunction "1_1") (pintype "passive"))
      (node (ref "C175") (pin "2") (pinfunction "2_2") (pintype "passive"))
      (node (ref "C176") (pin "2") (pinfunction "2_2") (pintype "passive"))
      (node (ref "C177") (pin "2") (pinfunction "2_2") (pintype "passive"))
      (node (ref "C178") (pin "2") (pinfunction "2_2") (pintype "passive"))
      (node (ref "C179") (pin "2") (pinfunction "2_2") (pintype "passive"))
      (node (ref "C18") (pin "2") (pinfunction "2_2") (pintype "passive"))
      (node (ref "C183") (pin "1") (pinfunction "1_1") (pintype "passive"))
      (node (ref "C184") (pin "1") (pinfunction "1_1") (pintype "passive"))
      (node (ref "C185") (pin "1") (pinfunction "1_1") (pintype "passive"))
      (node (ref "C186") (pin "1") (pinfunction "1_1") (pintype "passive"))
      (node (ref "C187") (pin "1") (pinfunction "1_1") (pintype "passive"))
      (node (ref "C201") (pin "1") (pinfunction "1_1") (pintype "passive"))
      (node (ref "C202") (pin "1") (pinfunction "1_1") (pintype "passive"))
      (node (ref "C203") (pin "1") (pinfunction "1_1") (pintype "passive"))
      (node (ref "C204") (pin "1") (pinfunction "1_1") (pintype "passive"))
      (node (ref "C205") (pin "1") (pinfunction "1_1") (pintype "passive"))
      (node (ref "C207") (pin "2") (pinfunction "2_2") (pintype "passive"))
      (node (ref "C208") (pin "2") (pinfunction "2_2") (pintype "passive"))
      (node (ref "C209") (pin "2") (pinfunction "2_2") (pintype "passive"))
      (node (ref "C21") (pin "2") (pinfunction "2_2") (pintype "passive"))
      (node (ref "C210") (pin "2") (pinfunction "2_2") (pintype "passive"))
      (node (ref "C211") (pin "2") (pinfunction "2_2") (pintype "passive"))
      (node (ref "C213") (pin "2") (pinfunction "2_2") (pintype "passive"))
      (node (ref "C214") (pin "2") (pinfunction "2_2") (pintype "passive"))
      (node (ref "C215") (pin "2") (pinfunction "2_2") (pintype "passive"))
      (node (ref "C23") (pin "1") (pinfunction "1_1") (pintype "passive"))
      (node (ref "C24") (pin "1") (pinfunction "1_1") (pintype "passive"))
      (node (ref "C245") (pin "1") (pinfunction "1_1") (pintype "passive"))
      (node (ref "C246") (pin "1") (pinfunction "1_1") (pintype "passive"))
      (node (ref "C247") (pin "1") (pinfunction "1_1") (pintype "passive"))
      (node (ref "C248") (pin "1") (pinfunction "1_1") (pintype "passive"))
      (node (ref "C249") (pin "2") (pinfunction "2_2") (pintype "passive"))
      (node (ref "C26") (pin "1") (pinfunction "1_1") (pintype "passive"))
      (node (ref "C27") (pin "2") (pinfunction "2_2") (pintype "passive"))
      (node (ref "C8") (pin "2") (pinfunction "2_2") (pintype "passive"))
      (node (ref "C9") (pin "1") (pinfunction "1_1") (pintype "passive"))
      (node (ref "C92") (pin "2") (pinfunction "2_2") (pintype "passive"))
      (node (ref "C94") (pin "2") (pinfunction "2_2") (pintype "passive"))
      (node (ref "C95") (pin "2") (pinfunction "2_2") (pintype "passive"))
      (node (ref "D14") (pin "1") (pinfunction "A_1") (pintype "passive"))
      (node (ref "D15") (pin "2") (pinfunction "K_2") (pintype "passive"))
      (node (ref "D16") (pin "2") (pinfunction "K_2") (pintype "passive"))
      (node (ref "D17") (pin "A") (pinfunction "A_A") (pintype "passive"))
      (node (ref "D18") (pin "1") (pinfunction "A_1") (pintype "passive"))
      (node (ref "D19") (pin "2") (pinfunction "K_2") (pintype "passive"))
      (node (ref "IC13") (pin "10") (pinfunction "PGND_10") (pintype "passive"))
      (node (ref "IC13") (pin "11") (pinfunction "PGND_11") (pintype "passive"))
      (node (ref "IC13") (pin "15") (pinfunction "AGND_15") (pintype "passive"))
      (node (ref "IC13") (pin "16") (pinfunction "NC_16") (pintype "passive"))
      (node (ref "IC13") (pin "5") (pinfunction "NC_5") (pintype "passive"))
      (node (ref "IC13") (pin "PAD") (pinfunction "PAD_GND_PAD") (pintype "passive"))
      (node (ref "IC14") (pin "5") (pinfunction "SGND_5") (pintype "passive"))
      (node (ref "IC14") (pin "9") (pinfunction "PGND_9") (pintype "passive"))
      (node (ref "IC14") (pin "PAD") (pinfunction "GND_PAD_PAD") (pintype "passive"))
      (node (ref "IC15") (pin "5") (pinfunction "SGND_5") (pintype "passive"))
      (node (ref "IC15") (pin "9") (pinfunction "PGND_9") (pintype "passive"))
      (node (ref "IC15") (pin "PAD") (pinfunction "GND_PAD_PAD") (pintype "passive"))
      (node (ref "IC21") (pin "1") (pinfunction "REF_1") (pintype "power_in"))
      (node (ref "IC21") (pin "2") (pinfunction "GND_2") (pintype "power_in"))
      (node (ref "IC22") (pin "1") (pinfunction "REF_1") (pintype "power_in"))
      (node (ref "IC22") (pin "2") (pinfunction "GND_2") (pintype "power_in"))
      (node (ref "IC24") (pin "1") (pinfunction "REF_1") (pintype "power_in"))
      (node (ref "IC24") (pin "2") (pinfunction "GND_2") (pintype "power_in"))
      (node (ref "Q2") (pin "1") (pinfunction "S_1") (pintype "passive"))
      (node (ref "Q2") (pin "2") (pinfunction "S_2") (pintype "passive"))
      (node (ref "Q2") (pin "3") (pinfunction "S_3") (pintype "passive"))
      (node (ref "Q4") (pin "1") (pinfunction "S_1") (pintype "passive"))
      (node (ref "Q4") (pin "2") (pinfunction "S_2") (pintype "passive"))
      (node (ref "Q4") (pin "3") (pinfunction "S_3") (pintype "passive"))
      (node (ref "R23") (pin "2") (pinfunction "2_2") (pintype "passive"))
      (node (ref "R24") (pin "1") (pinfunction "1_1") (pintype "passive"))
      (node (ref "R26") (pin "1") (pinfunction "1_1") (pintype "passive"))
      (node (ref "R31") (pin "1") (pinfunction "1_1") (pintype "passive"))
      (node (ref "R35") (pin "1") (pinfunction "1_1") (pintype "passive"))
      (node (ref "R36") (pin "1") (pinfunction "1_1") (pintype "passive"))
      (node (ref "R44") (pin "1") (pinfunction "1_1") (pintype "passive"))
    )
    (net (code "11") (name "Net-(C14-Pad2)") (class "Default")
      (node (ref "C14") (pin "2") (pinfunction "2_2") (pintype "passive"))
      (node (ref "R25") (pin "1") (pinfunction "1_1") (pintype "passive"))
    )
    (net (code "12") (name "Net-(C19-Pad2)") (class "Default")
      (node (ref "C19") (pin "2") (pinfunction "2_2") (pintype "passive"))
      (node (ref "R28") (pin "1") (pinfunction "1_1") (pintype "passive"))
    )
    (net (code "13") (name "Net-(C28-Pad2)") (class "Default")
      (node (ref "C28") (pin "2") (pinfunction "2_2") (pintype "passive"))
      (node (ref "R38") (pin "1") (pinfunction "1_1") (pintype "passive"))
    )
    (net (code "14") (name "Net-(C61-Pad2)") (class "Default")
      (node (ref "C61") (pin "2") (pinfunction "2_2") (pintype "passive"))
      (node (ref "R42") (pin "2") (pinfunction "2_2") (pintype "passive"))
    )
    (net (code "15") (name "Net-(C193-Pad2)") (class "Default")
      (node (ref "C193") (pin "2") (pinfunction "2_2") (pintype "passive"))
      (node (ref "R30") (pin "1") (pinfunction "1_1") (pintype "passive"))
    )
    (net (code "16") (name "Net-(D14-K)") (class "Default")
      (node (ref "C12") (pin "2") (pinfunction "2_2") (pintype "passive"))
      (node (ref "D14") (pin "2") (pinfunction "K_2") (pintype "passive"))
      (node (ref "IC14") (pin "12") (pinfunction "SW_12") (pintype "passive"))
      (node (ref "L1") (pin "1") (pinfunction "1_1") (pintype "passive"))
      (node (ref "Q1") (pin "1") (pinfunction "S_1") (pintype "passive"))
      (node (ref "Q1") (pin "2") (pinfunction "S_2") (pintype "passive"))
      (node (ref "Q1") (pin "3") (pinfunction "S_3") (pintype "passive"))
      (node (ref "Q2") (pin "5") (pinfunction "D_5") (pintype "passive"))
      (node (ref "Q2") (pin "6") (pinfunction "D_6") (pintype "passive"))
      (node (ref "Q2") (pin "7") (pinfunction "D_7") (pintype "passive"))
      (node (ref "Q2") (pin "8") (pinfunction "D_8") (pintype "passive"))
    )
    (net (code "17") (name "Net-(D15-A)") (class "Default")
      (node (ref "D15") (pin "1") (pinfunction "A_1") (pintype "passive"))
      (node (ref "R29") (pin "1") (pinfunction "1_1") (pintype "passive"))
    )
    (net (code "18") (name "Net-(D16-A)") (class "Default")
      (node (ref "D16") (pin "1") (pinfunction "A_1") (pintype "passive"))
      (node (ref "R34") (pin "1") (pinfunction "1_1") (pintype "passive"))
    )
    (net (code "19") (name "Net-(D18-K)") (class "Default")
      (node (ref "C25") (pin "2") (pinfunction "2_2") (pintype "passive"))
      (node (ref "D18") (pin "2") (pinfunction "K_2") (pintype "passive"))
      (node (ref "IC15") (pin "12") (pinfunction "SW_12") (pintype "passive"))
      (node (ref "L2") (pin "1") (pinfunction "1_1") (pintype "passive"))
      (node (ref "Q3") (pin "1") (pinfunction "S_1") (pintype "passive"))
      (node (ref "Q3") (pin "2") (pinfunction "S_2") (pintype "passive"))
      (node (ref "Q3") (pin "3") (pinfunction "S_3") (pintype "passive"))
      (node (ref "Q4") (pin "5") (pinfunction "D_5") (pintype "passive"))
      (node (ref "Q4") (pin "6") (pinfunction "D_6") (pintype "passive"))
      (node (ref "Q4") (pin "7") (pinfunction "D_7") (pintype "passive"))
      (node (ref "Q4") (pin "8") (pinfunction "D_8") (pintype "passive"))
    )
    (net (code "20") (name "Net-(D19-A)") (class "Default")
      (node (ref "D19") (pin "1") (pinfunction "A_1") (pintype "passive"))
      (node (ref "R41") (pin "1") (pinfunction "1_1") (pintype "passive"))
    )
    (net (code "21") (name "Net-(IC13-AVIN)") (class "Default")
      (node (ref "C13") (pin "2") (pinfunction "2_2") (pintype "passive"))
      (node (ref "IC13") (pin "14") (pinfunction "AVIN_14") (pintype "passive"))
      (node (ref "R16") (pin "1") (pinfunction "1_1") (pintype "passive"))
    )
    (net (code "22") (name "Net-(IC13-COMP)") (class "Default")
      (node (ref "IC13") (pin "4") (pinfunction "COMP_4") (pintype "passive"))
      (node (ref "R25") (pin "2") (pinfunction "2_2") (pintype "passive"))
    )
    (net (code "23") (name "Net-(IC13-FB)") (class "Default")
      (node (ref "IC13") (pin "2") (pinfunction "FB_2") (pintype "passive"))
      (node (ref "R17") (pin "1") (pinfunction "1_1") (pintype "passive"))
      (node (ref "R23") (pin "1") (pinfunction "1_1") (pintype "passive"))
    )
    (net (code "24") (name "Net-(IC13-SS{slash}TRK)") (class "Default")
      (node (ref "C16") (pin "2") (pinfunction "2_2") (pintype "passive"))
      (node (ref "IC13") (pin "1") (pinfunction "SS/TRK_1") (pintype "passive"))
    )
    (net (code "25") (name "Net-(IC13-SW-Pad8)") (class "Default")
      (node (ref "IC13") (pin "8") (pinfunction "SW_8") (pintype "passive"))
      (node (ref "IC13") (pin "9") (pinfunction "SW_9") (pintype "passive"))
      (node (ref "L8") (pin "1") (pinfunction "1_1") (pintype "passive"))
    )
    (net (code "26") (name "Net-(IC13-VCC)") (class "Default")
      (node (ref "C17") (pin "2") (pinfunction "2_2") (pintype "passive"))
      (node (ref "IC13") (pin "13") (pinfunction "VCC_13") (pintype "passive"))
    )
    (net (code "27") (name "Net-(IC14-BOOST)") (class "Default")
      (node (ref "C12") (pin "1") (pinfunction "1_1") (pintype "passive"))
      (node (ref "IC14") (pin "14") (pinfunction "BOOST_14") (pintype "passive"))
    )
    (net (code "28") (name "Net-(IC14-BP5)") (class "Default")
      (node (ref "C11") (pin "2") (pinfunction "2_2") (pintype "passive"))
      (node (ref "IC14") (pin "3") (pinfunction "BP5_3") (pintype "passive"))
    )
    (net (code "29") (name "Net-(IC14-BP10)") (class "Default")
      (node (ref "C18") (pin "1") (pinfunction "1_1") (pintype "passive"))
      (node (ref "IC14") (pin "11") (pinfunction "BP10_11") (pintype "passive"))
    )
    (net (code "30") (name "Net-(IC14-COMP)") (class "Default")
      (node (ref "C20") (pin "2") (pinfunction "2_2") (pintype "passive"))
      (node (ref "IC14") (pin "8") (pinfunction "COMP_8") (pintype "passive"))
      (node (ref "R30") (pin "2") (pinfunction "2_2") (pintype "passive"))
    )
    (net (code "31") (name "Net-(IC14-HDRV)") (class "Default")
      (node (ref "IC14") (pin "13") (pinfunction "HDRV_13") (pintype "passive"))
      (node (ref "Q1") (pin "4") (pinfunction "G_4") (pintype "passive"))
    )
    (net (code "32") (name "Net-(IC14-ILIM)") (class "Default")
      (node (ref "C10") (pin "1") (pinfunction "1_1") (pintype "passive"))
      (node (ref "IC14") (pin "16") (pinfunction "ILIM_16") (pintype "passive"))
      (node (ref "R15") (pin "1") (pinfunction "1_1") (pintype "passive"))
    )
    (net (code "33") (name "Net-(IC14-KFF)") (class "Default")
      (node (ref "IC14") (pin "1") (pinfunction "KFF_1") (pintype "passive"))
      (node (ref "R13") (pin "1") (pinfunction "1_1") (pintype "passive"))
    )
    (net (code "34") (name "Net-(IC14-LDRV)") (class "Default")
      (node (ref "IC14") (pin "10") (pinfunction "LDRV_10") (pintype "passive"))
      (node (ref "Q2") (pin "4") (pinfunction "G_4") (pintype "passive"))
    )
    (net (code "35") (name "Net-(IC14-RT)") (class "Default")
      (node (ref "IC14") (pin "2") (pinfunction "RT_2") (pintype "passive"))
      (node (ref "R24") (pin "2") (pinfunction "2_2") (pintype "passive"))
    )
    (net (code "36") (name "Net-(IC14-SS{slash}SD)") (class "Default")
      (node (ref "C15") (pin "2") (pinfunction "2_2") (pintype "passive"))
      (node (ref "IC14") (pin "6") (pinfunction "SS/SD_6") (pintype "passive"))
    )
    (net (code "37") (name "Net-(IC14-SYNC)") (class "Default")
      (node (ref "IC14") (pin "4") (pinfunction "SYNC_4") (pintype "passive"))
      (node (ref "R26") (pin "2") (pinfunction "2_2") (pintype "passive"))
    )
    (net (code "38") (name "Net-(IC14-VFB)") (class "Default")
      (node (ref "C19") (pin "1") (pinfunction "1_1") (pintype "passive"))
      (node (ref "C193") (pin "1") (pinfunction "1_1") (pintype "passive"))
      (node (ref "C20") (pin "1") (pinfunction "1_1") (pintype "passive"))
      (node (ref "IC14") (pin "7") (pinfunction "VFB_7") (pintype "passive"))
      (node (ref "R27") (pin "1") (pinfunction "1_1") (pintype "passive"))
      (node (ref "R31") (pin "2") (pinfunction "2_2") (pintype "passive"))
    )
    (net (code "39") (name "Net-(IC15-BOOST)") (class "Default")
      (node (ref "C25") (pin "1") (pinfunction "1_1") (pintype "passive"))
      (node (ref "IC15") (pin "14") (pinfunction "BOOST_14") (pintype "passive"))
    )
    (net (code "40") (name "Net-(IC15-BP5)") (class "Default")
      (node (ref "C24") (pin "2") (pinfunction "2_2") (pintype "passive"))
      (node (ref "IC15") (pin "3") (pinfunction "BP5_3") (pintype "passive"))
    )
    (net (code "41") (name "Net-(IC15-BP10)") (class "Default")
      (node (ref "C27") (pin "1") (pinfunction "1_1") (pintype "passive"))
      (node (ref "IC15") (pin "11") (pinfunction "BP10_11") (pintype "passive"))
    )
    (net (code "42") (name "Net-(IC15-COMP)") (class "Default")
      (node (ref "C29") (pin "2") (pinfunction "2_2") (pintype "passive"))
      (node (ref "IC15") (pin "8") (pinfunction "COMP_8") (pintype "passive"))
      (node (ref "R42") (pin "1") (pinfunction "1_1") (pintype "passive"))
    )
    (net (code "43") (name "Net-(IC15-HDRV)") (class "Default")
      (node (ref "IC15") (pin "13") (pinfunction "HDRV_13") (pintype "passive"))
      (node (ref "Q3") (pin "4") (pinfunction "G_4") (pintype "passive"))
    )
    (net (code "44") (name "Net-(IC15-ILIM)") (class "Default")
      (node (ref "C22") (pin "1") (pinfunction "1_1") (pintype "passive"))
      (node (ref "IC15") (pin "16") (pinfunction "ILIM_16") (pintype "passive"))
      (node (ref "R32") (pin "1") (pinfunction "1_1") (pintype "passive"))
    )
    (net (code "45") (name "Net-(IC15-KFF)") (class "Default")
      (node (ref "IC15") (pin "1") (pinfunction "KFF_1") (pintype "passive"))
      (node (ref "R33") (pin "1") (pinfunction "1_1") (pintype "passive"))
    )
    (net (code "46") (name "Net-(IC15-LDRV)") (class "Default")
      (node (ref "IC15") (pin "10") (pinfunction "LDRV_10") (pintype "passive"))
      (node (ref "Q4") (pin "4") (pinfunction "G_4") (pintype "passive"))
    )
    (net (code "47") (name "Net-(IC15-RT)") (class "Default")
      (node (ref "IC15") (pin "2") (pinfunction "RT_2") (pintype "passive"))
      (node (ref "R35") (pin "2") (pinfunction "2_2") (pintype "passive"))
    )
    (net (code "48") (name "Net-(IC15-SS{slash}SD)") (class "Default")
      (node (ref "C26") (pin "2") (pinfunction "2_2") (pintype "passive"))
      (node (ref "IC15") (pin "6") (pinfunction "SS/SD_6") (pintype "passive"))
    )
    (net (code "49") (name "Net-(IC15-SYNC)") (class "Default")
      (node (ref "IC15") (pin "4") (pinfunction "SYNC_4") (pintype "passive"))
      (node (ref "R36") (pin "2") (pinfunction "2_2") (pintype "passive"))
    )
    (net (code "50") (name "Net-(IC15-VFB)") (class "Default")
      (node (ref "C28") (pin "1") (pinfunction "1_1") (pintype "passive"))
      (node (ref "C29") (pin "1") (pinfunction "1_1") (pintype "passive"))
      (node (ref "C61") (pin "1") (pinfunction "1_1") (pintype "passive"))
      (node (ref "IC15") (pin "7") (pinfunction "VFB_7") (pintype "passive"))
      (node (ref "R37") (pin "1") (pinfunction "1_1") (pintype "passive"))
      (node (ref "R44") (pin "2") (pinfunction "2_2") (pintype "passive"))
    )
    (net (code "51") (name "Net-(IC21-IN+)") (class "Default")
      (node (ref "C140") (pin "2") (pinfunction "2_2") (pintype "passive"))
      (node (ref "IC21") (pin "4") (pinfunction "IN+_4") (pintype "passive"))
      (node (ref "R103") (pin "1") (pinfunction "1_1") (pintype "passive"))
    )
    (net (code "52") (name "Net-(IC21-IN-)") (class "Default")
      (node (ref "C140") (pin "1") (pinfunction "1_1") (pintype "passive"))
      (node (ref "IC21") (pin "5") (pinfunction "IN-_5") (pintype "passive"))
      (node (ref "R104") (pin "1") (pinfunction "1_1") (pintype "passive"))
    )
    (net (code "53") (name "Net-(IC22-IN+)") (class "Default")
      (node (ref "C241") (pin "2") (pinfunction "2_2") (pintype "passive"))
      (node (ref "IC22") (pin "4") (pinfunction "IN+_4") (pintype "passive"))
      (node (ref "R105") (pin "1") (pinfunction "1_1") (pintype "passive"))
    )
    (net (code "54") (name "Net-(IC22-IN-)") (class "Default")
      (node (ref "C241") (pin "1") (pinfunction "1_1") (pintype "passive"))
      (node (ref "IC22") (pin "5") (pinfunction "IN-_5") (pintype "passive"))
      (node (ref "R106") (pin "1") (pinfunction "1_1") (pintype "passive"))
    )
    (net (code "55") (name "Net-(IC24-IN+)") (class "Default")
      (node (ref "C242") (pin "2") (pinfunction "2_2") (pintype "passive"))
      (node (ref "IC24") (pin "4") (pinfunction "IN+_4") (pintype "passive"))
      (node (ref "R107") (pin "1") (pinfunction "1_1") (pintype "passive"))
    )
    (net (code "56") (name "Net-(IC24-IN-)") (class "Default")
      (node (ref "C242") (pin "1") (pinfunction "1_1") (pintype "passive"))
      (node (ref "IC24") (pin "5") (pinfunction "IN-_5") (pintype "passive"))
      (node (ref "R108") (pin "1") (pinfunction "1_1") (pintype "passive"))
    )
    (net (code "57") (name "Net-(L1-Pad2)") (class "Default")
      (node (ref "L1") (pin "2") (pinfunction "2_2") (pintype "passive"))
      (node (ref "R105") (pin "2") (pinfunction "2_2") (pintype "passive"))
      (node (ref "R97") (pin "2") (pinfunction "2_2") (pintype "passive"))
    )
    (net (code "58") (name "Net-(L2-Pad2)") (class "Default")
      (node (ref "L2") (pin "2") (pinfunction "2_2") (pintype "passive"))
      (node (ref "R107") (pin "2") (pinfunction "2_2") (pintype "passive"))
      (node (ref "R98") (pin "2") (pinfunction "2_2") (pintype "passive"))
    )
    (net (code "59") (name "Net-(L8-Pad2)") (class "Default")
      (node (ref "L8") (pin "2") (pinfunction "2_2") (pintype "passive"))
      (node (ref "R103") (pin "2") (pinfunction "2_2") (pintype "passive"))
      (node (ref "R96") (pin "2") (pinfunction "2_2") (pintype "passive"))
    )
    (net (code "60") (name "unconnected-(IC13-PGOOD-Pad3)") (class "Default")
      (node (ref "IC13") (pin "3") (pinfunction "PGOOD_3") (pintype "passive"))
    )
  )
)
